# 05-SNESDRONE_Direct_IO_LEVEL_SHIFTER_2.net
KiCad netlist of a schematic drawn in Altium Designer
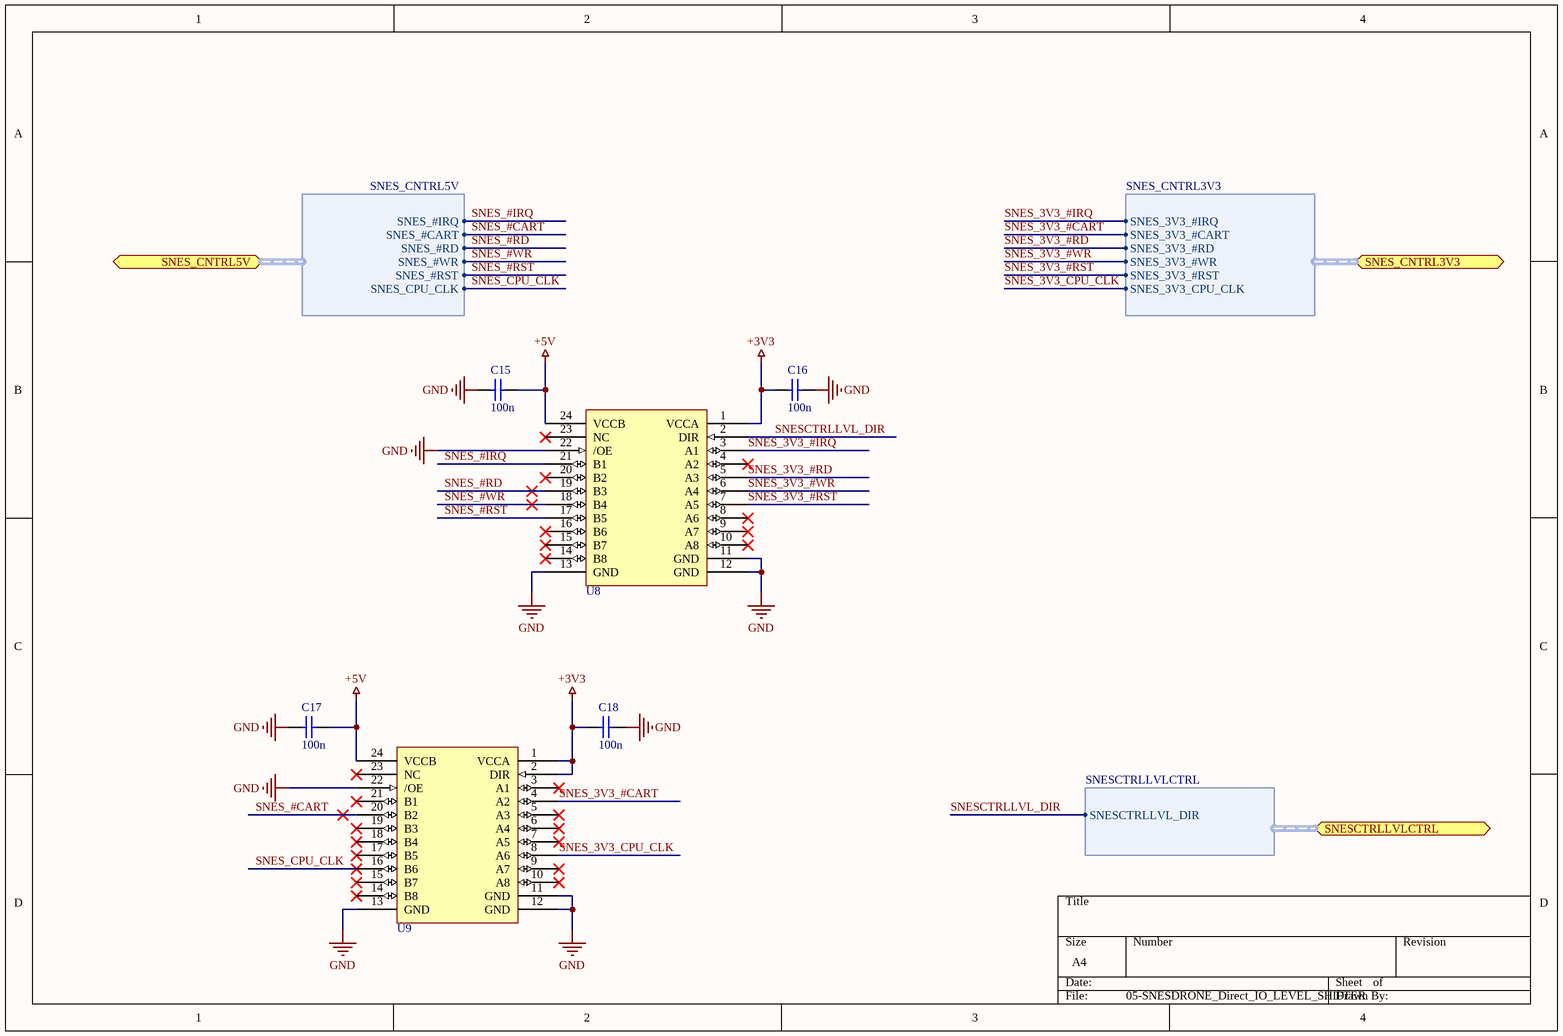
[diagram p0: 05-SNESDRONE_Direct_IO_LEVEL_SHIFTER_2.SchDoc]

(export (version "E")
  (design (tool "Eeschema 10.0.6"))
  (components
    (comp (ref "C15")
      (value "100n")
      (footprint "cap_0603")
      (description "Capacitor")
      (fields (field (name "Comment") "cap_0603"))
      (libsource (lib "mycomponents") (part "cap_0603"))
    )
    (comp (ref "C16")
      (value "100n")
      (footprint "cap_0603")
      (description "Capacitor")
      (fields (field (name "Comment") "cap_0603"))
      (libsource (lib "mycomponents") (part "cap_0603"))
    )
    (comp (ref "C17")
      (value "100n")
      (footprint "cap_0603")
      (description "Capacitor")
      (fields (field (name "Comment") "cap_0603"))
      (libsource (lib "mycomponents") (part "cap_0603"))
    )
    (comp (ref "C18")
      (value "100n")
      (footprint "cap_0603")
      (description "Capacitor")
      (fields (field (name "Comment") "cap_0603"))
      (libsource (lib "mycomponents") (part "cap_0603"))
    )
    (comp (ref "U8")
      (value "IC_SN74LVCC3245APWR")
      (footprint "TSSOP24")
      (description "Bus-Transceiver, Produktreihe LVC, 8 Eingänge, 50mA, 7ns, 2.3V bis 5.5V, TSSOP 24")
      (libsource (lib "mycomponents") (part "IC_SN74LVCC3245APWR"))
    )
    (comp (ref "U9")
      (value "IC_SN74LVCC3245APWR")
      (footprint "TSSOP24")
      (description "Bus-Transceiver, Produktreihe LVC, 8 Eingänge, 50mA, 7ns, 2.3V bis 5.5V, TSSOP 24")
      (libsource (lib "mycomponents") (part "IC_SN74LVCC3245APWR"))
    )
  )
  (nets
    (net (code "4") (name "+3V3") (class "Default")
      (node (ref "C16") (pin "2") (pinfunction "2_2") (pintype "passive"))
      (node (ref "C18") (pin "2") (pinfunction "2_2") (pintype "passive"))
      (node (ref "U8") (pin "1") (pinfunction "VCCA_1") (pintype "power_in"))
      (node (ref "U9") (pin "1") (pinfunction "VCCA_1") (pintype "power_in"))
      (node (ref "U9") (pin "2") (pinfunction "DIR_2") (pintype "input"))
    )
    (net (code "5") (name "+5V") (class "Default")
      (node (ref "C15") (pin "1") (pinfunction "1_1") (pintype "passive"))
      (node (ref "C17") (pin "1") (pinfunction "1_1") (pintype "passive"))
      (node (ref "U8") (pin "24") (pinfunction "VCCB_24") (pintype "power_in"))
      (node (ref "U9") (pin "24") (pinfunction "VCCB_24") (pintype "power_in"))
    )
    (net (code "6") (name "/SNESCTRLLVL_DIR") (class "Default")
      (node (ref "U8") (pin "2") (pinfunction "DIR_2") (pintype "input"))
    )
    (net (code "7") (name "/SNES_#CART") (class "Default")
      (node (ref "U9") (pin "20") (pinfunction "B2_20") (pintype "bidirectional"))
    )
    (net (code "8") (name "/SNES_#IRQ") (class "Default")
      (node (ref "U8") (pin "21") (pinfunction "B1_21") (pintype "bidirectional"))
    )
    (net (code "9") (name "/SNES_#RD") (class "Default")
      (node (ref "U8") (pin "19") (pinfunction "B3_19") (pintype "bidirectional"))
    )
    (net (code "10") (name "/SNES_#RST") (class "Default")
      (node (ref "U8") (pin "17") (pinfunction "B5_17") (pintype "bidirectional"))
    )
    (net (code "11") (name "/SNES_#WR") (class "Default")
      (node (ref "U8") (pin "18") (pinfunction "B4_18") (pintype "bidirectional"))
    )
    (net (code "12") (name "/SNES_3V3_#CART") (class "Default")
      (node (ref "U9") (pin "4") (pinfunction "A2_4") (pintype "bidirectional"))
    )
    (net (code "13") (name "/SNES_3V3_#IRQ") (class "Default")
      (node (ref "U8") (pin "3") (pinfunction "A1_3") (pintype "bidirectional"))
    )
    (net (code "14") (name "/SNES_3V3_#RD") (class "Default")
      (node (ref "U8") (pin "5") (pinfunction "A3_5") (pintype "bidirectional"))
    )
    (net (code "15") (name "/SNES_3V3_#RST") (class "Default")
      (node (ref "U8") (pin "7") (pinfunction "A5_7") (pintype "bidirectional"))
    )
    (net (code "16") (name "/SNES_3V3_#WR") (class "Default")
      (node (ref "U8") (pin "6") (pinfunction "A4_6") (pintype "bidirectional"))
    )
    (net (code "17") (name "/SNES_3V3_CPU_CLK") (class "Default")
      (node (ref "U9") (pin "8") (pinfunction "A6_8") (pintype "bidirectional"))
    )
    (net (code "18") (name "/SNES_CPU_CLK") (class "Default")
      (node (ref "U9") (pin "16") (pinfunction "B6_16") (pintype "bidirectional"))
    )
    (net (code "22") (name "GND") (class "Default")
      (node (ref "C15") (pin "2") (pinfunction "2_2") (pintype "passive"))
      (node (ref "C16") (pin "1") (pinfunction "1_1") (pintype "passive"))
      (node (ref "C17") (pin "2") (pinfunction "2_2") (pintype "passive"))
      (node (ref "C18") (pin "1") (pinfunction "1_1") (pintype "passive"))
      (node (ref "U8") (pin "11") (pinfunction "GND_11") (pintype "power_in"))
      (node (ref "U8") (pin "12") (pinfunction "GND_12") (pintype "power_in"))
      (node (ref "U8") (pin "13") (pinfunction "GND_13") (pintype "power_in"))
      (node (ref "U8") (pin "22") (pinfunction "/OE_22") (pintype "input"))
      (node (ref "U9") (pin "11") (pinfunction "GND_11") (pintype "power_in"))
      (node (ref "U9") (pin "12") (pinfunction "GND_12") (pintype "power_in"))
      (node (ref "U9") (pin "13") (pinfunction "GND_13") (pintype "power_in"))
      (node (ref "U9") (pin "22") (pinfunction "/OE_22") (pintype "input"))
    )
    (net (code "23") (name "unconnected-(U8-A2-Pad4)") (class "Default")
      (node (ref "U8") (pin "4") (pinfunction "A2_4") (pintype "bidirectional+no_connect"))
    )
    (net (code "24") (name "unconnected-(U8-A6-Pad8)") (class "Default")
      (node (ref "U8") (pin "8") (pinfunction "A6_8") (pintype "bidirectional+no_connect"))
    )
    (net (code "25") (name "unconnected-(U8-A7-Pad9)") (class "Default")
      (node (ref "U8") (pin "9") (pinfunction "A7_9") (pintype "bidirectional+no_connect"))
    )
    (net (code "26") (name "unconnected-(U8-A8-Pad10)") (class "Default")
      (node (ref "U8") (pin "10") (pinfunction "A8_10") (pintype "bidirectional+no_connect"))
    )
    (net (code "27") (name "unconnected-(U8-B2-Pad20)") (class "Default")
      (node (ref "U8") (pin "20") (pinfunction "B2_20") (pintype "bidirectional+no_connect"))
    )
    (net (code "28") (name "unconnected-(U8-B6-Pad16)") (class "Default")
      (node (ref "U8") (pin "16") (pinfunction "B6_16") (pintype "bidirectional+no_connect"))
    )
    (net (code "29") (name "unconnected-(U8-B7-Pad15)") (class "Default")
      (node (ref "U8") (pin "15") (pinfunction "B7_15") (pintype "bidirectional+no_connect"))
    )
    (net (code "30") (name "unconnected-(U8-B8-Pad14)") (class "Default")
      (node (ref "U8") (pin "14") (pinfunction "B8_14") (pintype "bidirectional+no_connect"))
    )
    (net (code "31") (name "unconnected-(U8-NC-Pad23)") (class "Default")
      (node (ref "U8") (pin "23") (pinfunction "NC_23") (pintype "passive+no_connect"))
    )
    (net (code "32") (name "unconnected-(U9-A1-Pad3)") (class "Default")
      (node (ref "U9") (pin "3") (pinfunction "A1_3") (pintype "bidirectional+no_connect"))
    )
    (net (code "33") (name "unconnected-(U9-A3-Pad5)") (class "Default")
      (node (ref "U9") (pin "5") (pinfunction "A3_5") (pintype "bidirectional+no_connect"))
    )
    (net (code "34") (name "unconnected-(U9-A4-Pad6)") (class "Default")
      (node (ref "U9") (pin "6") (pinfunction "A4_6") (pintype "bidirectional+no_connect"))
    )
    (net (code "35") (name "unconnected-(U9-A5-Pad7)") (class "Default")
      (node (ref "U9") (pin "7") (pinfunction "A5_7") (pintype "bidirectional+no_connect"))
    )
    (net (code "36") (name "unconnected-(U9-A7-Pad9)") (class "Default")
      (node (ref "U9") (pin "9") (pinfunction "A7_9") (pintype "bidirectional+no_connect"))
    )
    (net (code "37") (name "unconnected-(U9-A8-Pad10)") (class "Default")
      (node (ref "U9") (pin "10") (pinfunction "A8_10") (pintype "bidirectional+no_connect"))
    )
    (net (code "38") (name "unconnected-(U9-B1-Pad21)") (class "Default")
      (node (ref "U9") (pin "21") (pinfunction "B1_21") (pintype "bidirectional+no_connect"))
    )
    (net (code "39") (name "unconnected-(U9-B3-Pad19)") (class "Default")
      (node (ref "U9") (pin "19") (pinfunction "B3_19") (pintype "bidirectional+no_connect"))
    )
    (net (code "40") (name "unconnected-(U9-B4-Pad18)") (class "Default")
      (node (ref "U9") (pin "18") (pinfunction "B4_18") (pintype "bidirectional+no_connect"))
    )
    (net (code "41") (name "unconnected-(U9-B5-Pad17)") (class "Default")
      (node (ref "U9") (pin "17") (pinfunction "B5_17") (pintype "bidirectional+no_connect"))
    )
    (net (code "42") (name "unconnected-(U9-B7-Pad15)") (class "Default")
      (node (ref "U9") (pin "15") (pinfunction "B7_15") (pintype "bidirectional+no_connect"))
    )
    (net (code "43") (name "unconnected-(U9-B8-Pad14)") (class "Default")
      (node (ref "U9") (pin "14") (pinfunction "B8_14") (pintype "bidirectional+no_connect"))
    )
    (net (code "44") (name "unconnected-(U9-NC-Pad23)") (class "Default")
      (node (ref "U9") (pin "23") (pinfunction "NC_23") (pintype "passive+no_connect"))
    )
  )
)
